# Final_Driver_Concept.net
KiCad netlist of a schematic drawn in EAGLE
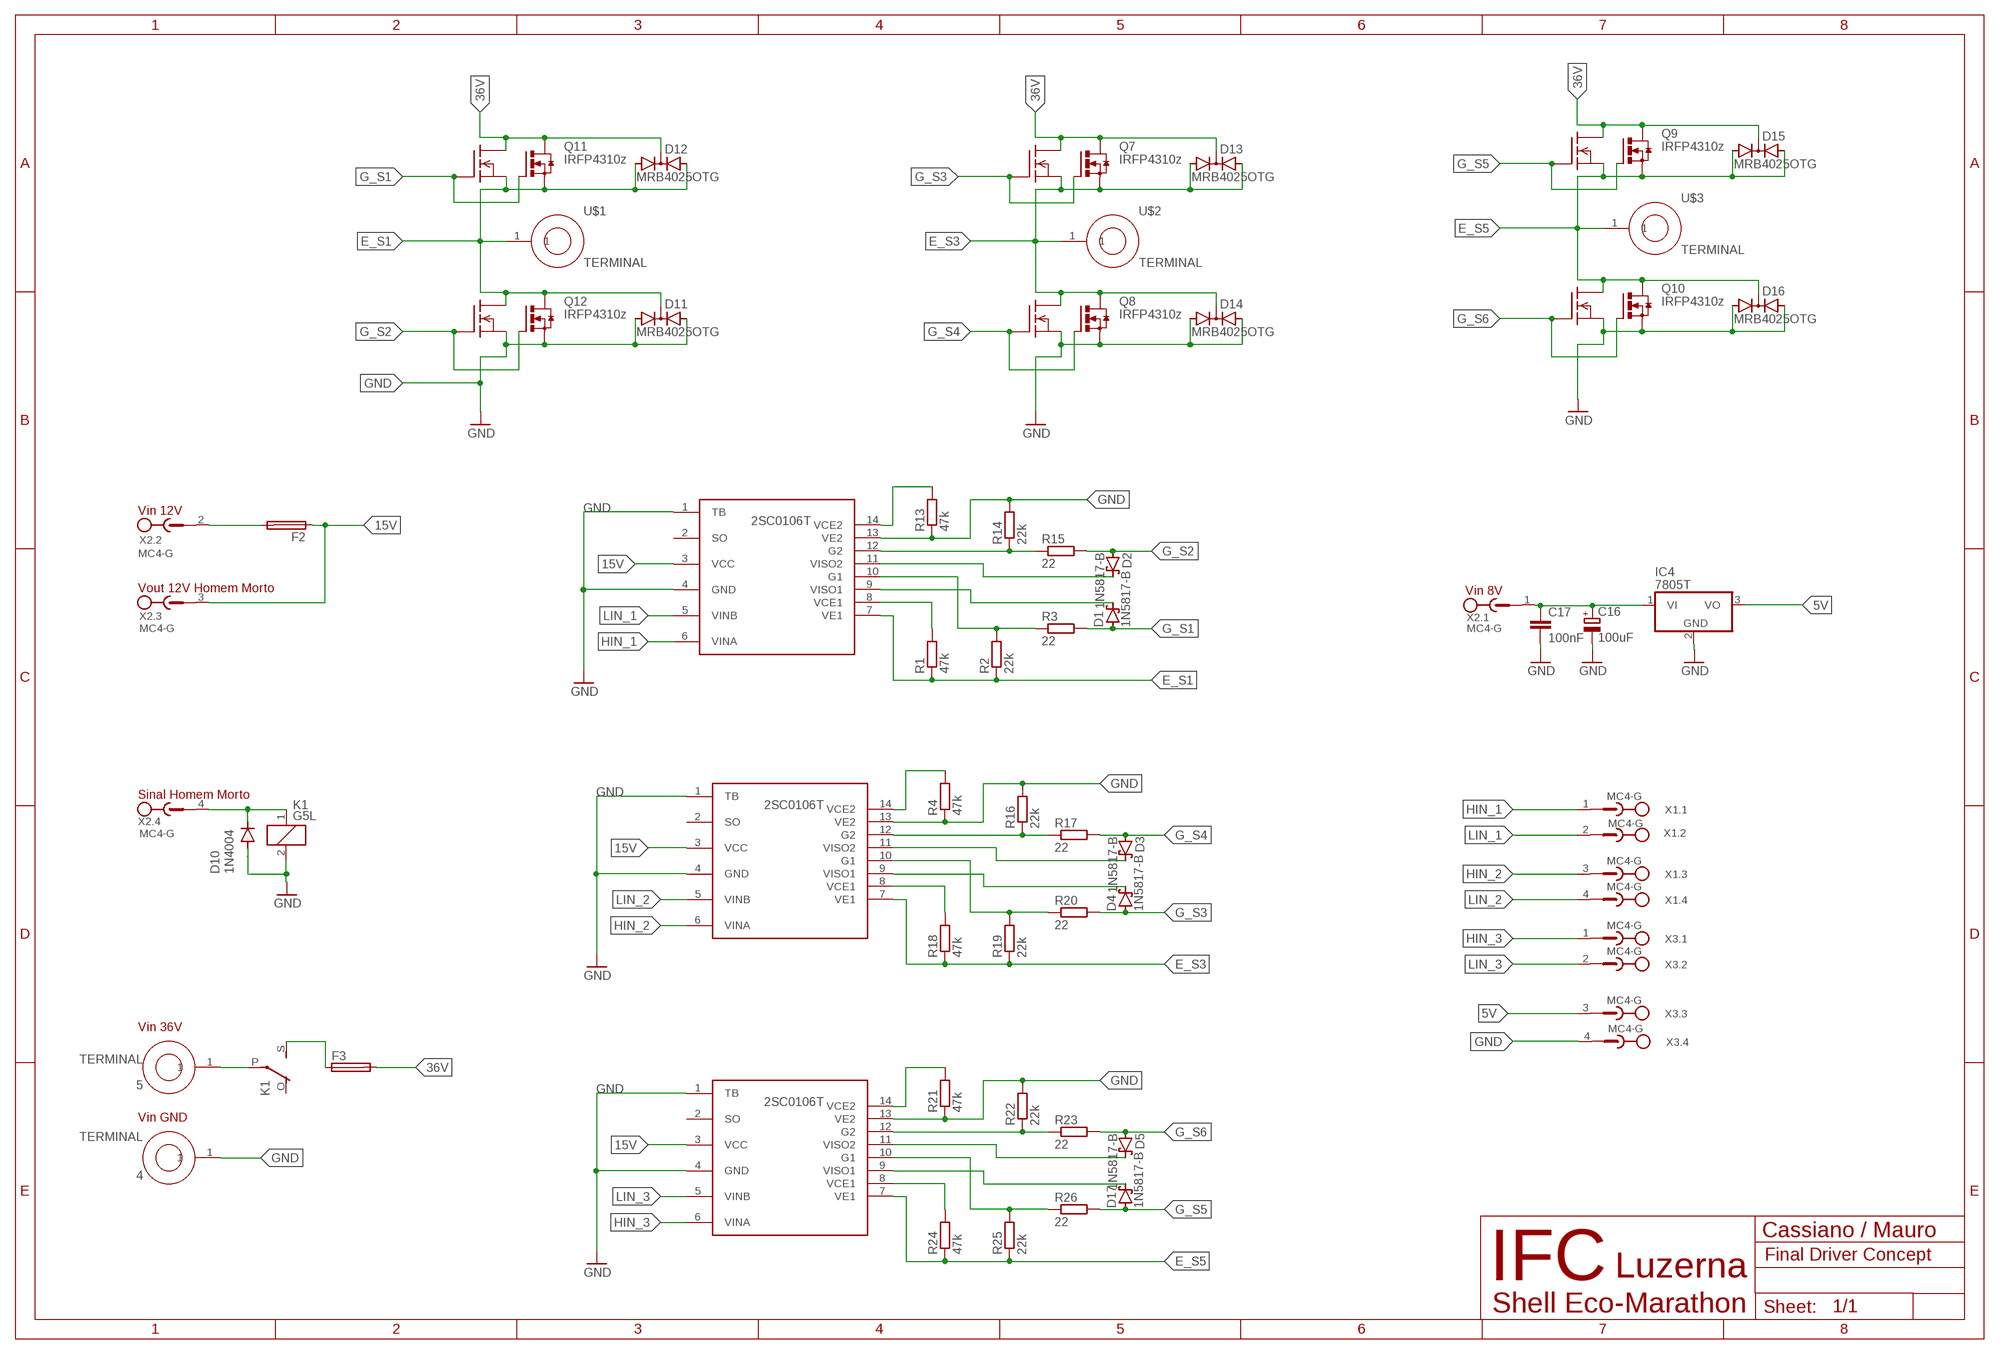
[diagram p0: schematic, sheet 1]

(export (version "E")
  (design (tool "Eeschema 10.0.6"))
  (components
    (comp (ref "4")
      (value "TERMINAL")
      (footprint "eagle-import:TERMINAL")
      (libsource (lib "eagle-import") (part "TERMINAL"))
    )
    (comp (ref "5")
      (value "TERMINAL")
      (footprint "eagle-import:TERMINAL")
      (libsource (lib "eagle-import") (part "TERMINAL"))
    )
    (comp (ref "C16")
      (value "100uF")
      (footprint "eagle-import:E2,5-7")
      (libsource (lib "eagle-import") (part "CPOL-EUE2.5-7"))
    )
    (comp (ref "C17")
      (value "100nF")
      (footprint "eagle-import:C050-045X075")
      (libsource (lib "eagle-import") (part "C-EU050-045X075"))
    )
    (comp (ref "D1")
      (value "1N5817-B")
      (footprint "eagle-import:DO41-7.6")
      (libsource (lib "eagle-import") (part "1N5817-B"))
    )
    (comp (ref "D2")
      (value "1N5817-B")
      (footprint "eagle-import:DO41-7.6")
      (libsource (lib "eagle-import") (part "1N5817-B"))
    )
    (comp (ref "D3")
      (value "1N5817-B")
      (footprint "eagle-import:DO41-7.6")
      (libsource (lib "eagle-import") (part "1N5817-B"))
    )
    (comp (ref "D4")
      (value "1N5817-B")
      (footprint "eagle-import:DO41-7.6")
      (libsource (lib "eagle-import") (part "1N5817-B"))
    )
    (comp (ref "D5")
      (value "1N5817-B")
      (footprint "eagle-import:DO41-7.6")
      (libsource (lib "eagle-import") (part "1N5817-B"))
    )
    (comp (ref "D10")
      (value "1N4004")
      (footprint "eagle-import:DO41-10")
      (libsource (lib "eagle-import") (part "1N4004"))
    )
    (comp (ref "D11")
      (value "MRB4025OTG")
      (footprint "eagle-import:TO220AB")
      (libsource (lib "eagle-import") (part "MUR620CT"))
    )
    (comp (ref "D12")
      (value "MRB4025OTG")
      (footprint "eagle-import:TO220AB")
      (libsource (lib "eagle-import") (part "MUR620CT"))
    )
    (comp (ref "D13")
      (value "MRB4025OTG")
      (footprint "eagle-import:TO220AB")
      (libsource (lib "eagle-import") (part "MUR620CT"))
    )
    (comp (ref "D14")
      (value "MRB4025OTG")
      (footprint "eagle-import:TO220AB")
      (libsource (lib "eagle-import") (part "MUR620CT"))
    )
    (comp (ref "D15")
      (value "MRB4025OTG")
      (footprint "eagle-import:TO220AB")
      (libsource (lib "eagle-import") (part "MUR620CT"))
    )
    (comp (ref "D16")
      (value "MRB4025OTG")
      (footprint "eagle-import:TO220AB")
      (libsource (lib "eagle-import") (part "MUR620CT"))
    )
    (comp (ref "D17")
      (value "1N5817-B")
      (footprint "eagle-import:DO41-7.6")
      (libsource (lib "eagle-import") (part "1N5817-B"))
    )
    (comp (ref "F2")
      (value "SH22,5A")
      (footprint "eagle-import:SH22,5A")
      (fields (field (name "MPN") "0031.7701.11"))
      (libsource (lib "eagle-import") (part "SH22,5A"))
    )
    (comp (ref "F3")
      (value "SH22,5A")
      (footprint "eagle-import:SH22,5A")
      (fields (field (name "MPN") "0031.7701.11"))
      (libsource (lib "eagle-import") (part "SH22,5A"))
    )
    (comp (ref "GATEDRIVER1")
      (value "2SC0106T1")
      (footprint "eagle-import:2SC0106T")
      (libsource (lib "eagle-import") (part "2SC0106T1"))
    )
    (comp (ref "GATEDRIVER2")
      (value "2SC0106T1")
      (footprint "eagle-import:2SC0106T")
      (libsource (lib "eagle-import") (part "2SC0106T1"))
    )
    (comp (ref "GATEDRIVER3")
      (value "2SC0106T1")
      (footprint "eagle-import:2SC0106T")
      (libsource (lib "eagle-import") (part "2SC0106T1"))
    )
    (comp (ref "IC4")
      (value "7805T")
      (footprint "eagle-import:TO220H")
      (libsource (lib "eagle-import") (part "78T05"))
    )
    (comp (ref "K1")
      (value "G5L")
      (footprint "eagle-import:G5LE")
      (libsource (lib "eagle-import") (part "G5L"))
    )
    (comp (ref "Q1")
      (value "IRF540")
      (footprint "eagle-import:TO220")
      (libsource (lib "eagle-import") (part "IRF540"))
    )
    (comp (ref "Q2")
      (value "IRF540")
      (footprint "eagle-import:TO220")
      (libsource (lib "eagle-import") (part "IRF540"))
    )
    (comp (ref "Q3")
      (value "IRF540")
      (footprint "eagle-import:TO220")
      (libsource (lib "eagle-import") (part "IRF540"))
    )
    (comp (ref "Q4")
      (value "IRF540")
      (footprint "eagle-import:TO220")
      (libsource (lib "eagle-import") (part "IRF540"))
    )
    (comp (ref "Q5")
      (value "IRF540")
      (footprint "eagle-import:TO220")
      (libsource (lib "eagle-import") (part "IRF540"))
    )
    (comp (ref "Q6")
      (value "IRF540")
      (footprint "eagle-import:TO220")
      (libsource (lib "eagle-import") (part "IRF540"))
    )
    (comp (ref "Q7")
      (value "IRFP4310z")
      (footprint "eagle-import:TO247BH")
      (libsource (lib "eagle-import") (part "IRFP240-H"))
    )
    (comp (ref "Q8")
      (value "IRFP4310z")
      (footprint "eagle-import:TO247BH")
      (libsource (lib "eagle-import") (part "IRFP240-H"))
    )
    (comp (ref "Q9")
      (value "IRFP4310z")
      (footprint "eagle-import:TO247BH")
      (libsource (lib "eagle-import") (part "IRFP240-H"))
    )
    (comp (ref "Q10")
      (value "IRFP4310z")
      (footprint "eagle-import:TO247BH")
      (libsource (lib "eagle-import") (part "IRFP240-H"))
    )
    (comp (ref "Q11")
      (value "IRFP4310z")
      (footprint "eagle-import:TO247BH")
      (libsource (lib "eagle-import") (part "IRFP240-H"))
    )
    (comp (ref "Q12")
      (value "IRFP4310z")
      (footprint "eagle-import:TO247BH")
      (libsource (lib "eagle-import") (part "IRFP240-H"))
    )
    (comp (ref "R1")
      (value "47k")
      (footprint "eagle-import:0204_7")
      (libsource (lib "eagle-import") (part "R-EU_0204/7"))
    )
    (comp (ref "R2")
      (value "22k")
      (footprint "eagle-import:0204_7")
      (libsource (lib "eagle-import") (part "R-EU_0204/7"))
    )
    (comp (ref "R3")
      (value "22")
      (footprint "eagle-import:0204_7")
      (libsource (lib "eagle-import") (part "R-EU_0204/7"))
    )
    (comp (ref "R4")
      (value "47k")
      (footprint "eagle-import:0204_7")
      (libsource (lib "eagle-import") (part "R-EU_0204/7"))
    )
    (comp (ref "R13")
      (value "47k")
      (footprint "eagle-import:0204_7")
      (libsource (lib "eagle-import") (part "R-EU_0204/7"))
    )
    (comp (ref "R14")
      (value "22k")
      (footprint "eagle-import:0204_7")
      (libsource (lib "eagle-import") (part "R-EU_0204/7"))
    )
    (comp (ref "R15")
      (value "22")
      (footprint "eagle-import:0204_7")
      (libsource (lib "eagle-import") (part "R-EU_0204/7"))
    )
    (comp (ref "R16")
      (value "22k")
      (footprint "eagle-import:0204_7")
      (libsource (lib "eagle-import") (part "R-EU_0204/7"))
    )
    (comp (ref "R17")
      (value "22")
      (footprint "eagle-import:0204_7")
      (libsource (lib "eagle-import") (part "R-EU_0204/7"))
    )
    (comp (ref "R18")
      (value "47k")
      (footprint "eagle-import:0204_7")
      (libsource (lib "eagle-import") (part "R-EU_0204/7"))
    )
    (comp (ref "R19")
      (value "22k")
      (footprint "eagle-import:0204_7")
      (libsource (lib "eagle-import") (part "R-EU_0204/7"))
    )
    (comp (ref "R20")
      (value "22")
      (footprint "eagle-import:0204_7")
      (libsource (lib "eagle-import") (part "R-EU_0204/7"))
    )
    (comp (ref "R21")
      (value "47k")
      (footprint "eagle-import:0204_7")
      (libsource (lib "eagle-import") (part "R-EU_0204/7"))
    )
    (comp (ref "R22")
      (value "22k")
      (footprint "eagle-import:0204_7")
      (libsource (lib "eagle-import") (part "R-EU_0204/7"))
    )
    (comp (ref "R23")
      (value "22")
      (footprint "eagle-import:0204_7")
      (libsource (lib "eagle-import") (part "R-EU_0204/7"))
    )
    (comp (ref "R24")
      (value "47k")
      (footprint "eagle-import:0204_7")
      (libsource (lib "eagle-import") (part "R-EU_0204/7"))
    )
    (comp (ref "R25")
      (value "22k")
      (footprint "eagle-import:0204_7")
      (libsource (lib "eagle-import") (part "R-EU_0204/7"))
    )
    (comp (ref "R26")
      (value "22")
      (footprint "eagle-import:0204_7")
      (libsource (lib "eagle-import") (part "R-EU_0204/7"))
    )
    (comp (ref "U$1")
      (value "TERMINAL")
      (footprint "eagle-import:TERMINAL")
      (libsource (lib "eagle-import") (part "TERMINAL"))
    )
    (comp (ref "U$2")
      (value "TERMINAL")
      (footprint "eagle-import:TERMINAL")
      (libsource (lib "eagle-import") (part "TERMINAL"))
    )
    (comp (ref "U$3")
      (value "TERMINAL")
      (footprint "eagle-import:TERMINAL")
      (libsource (lib "eagle-import") (part "TERMINAL"))
    )
    (comp (ref "X1")
      (value "MC4-G")
      (footprint "eagle-import:MC4-G")
      (libsource (lib "eagle-import") (part "MC4-G"))
    )
    (comp (ref "X2")
      (value "MC4-G")
      (footprint "eagle-import:MC4-G")
      (libsource (lib "eagle-import") (part "MC4-G"))
    )
    (comp (ref "X3")
      (value "MC4-G")
      (footprint "eagle-import:MC4-G")
      (libsource (lib "eagle-import") (part "MC4-G"))
    )
  )
  (nets
    (net (code "1") (name "5V") (class "Default")
      (node (ref "IC4") (pin "3") (pinfunction "VO_3") (pintype "passive"))
      (node (ref "X3") (pin "3") (pinfunction "SK_3") (pintype "passive"))
    )
    (net (code "2") (name "15V") (class "Default")
      (node (ref "F2") (pin "1") (pinfunction "1_1") (pintype "passive"))
      (node (ref "GATEDRIVER1") (pin "3") (pinfunction "VCC_3") (pintype "power_in"))
      (node (ref "GATEDRIVER2") (pin "3") (pinfunction "VCC_3") (pintype "power_in"))
      (node (ref "GATEDRIVER3") (pin "3") (pinfunction "VCC_3") (pintype "power_in"))
      (node (ref "X2") (pin "3") (pinfunction "SK_3") (pintype "passive"))
    )
    (net (code "3") (name "36V") (class "Default")
      (node (ref "D12") (pin "C") (pinfunction "C_C") (pintype "passive"))
      (node (ref "D13") (pin "C") (pinfunction "C_C") (pintype "passive"))
      (node (ref "D15") (pin "C") (pinfunction "C_C") (pintype "passive"))
      (node (ref "F3") (pin "2") (pinfunction "2_2") (pintype "passive"))
      (node (ref "Q1") (pin "2") (pinfunction "D_2") (pintype "passive"))
      (node (ref "Q11") (pin "D") (pinfunction "D_D") (pintype "passive"))
      (node (ref "Q3") (pin "2") (pinfunction "D_2") (pintype "passive"))
      (node (ref "Q5") (pin "2") (pinfunction "D_2") (pintype "passive"))
      (node (ref "Q7") (pin "D") (pinfunction "D_D") (pintype "passive"))
      (node (ref "Q9") (pin "D") (pinfunction "D_D") (pintype "passive"))
    )
    (net (code "4") (name "E_S1") (class "Default")
      (node (ref "D11") (pin "C") (pinfunction "C_C") (pintype "passive"))
      (node (ref "D12") (pin "A1") (pinfunction "A1_A1") (pintype "passive"))
      (node (ref "D12") (pin "A2") (pinfunction "A2_A2") (pintype "passive"))
      (node (ref "GATEDRIVER1") (pin "7") (pinfunction "VE1_7") (pintype "bidirectional"))
      (node (ref "Q1") (pin "3") (pinfunction "S_3") (pintype "passive"))
      (node (ref "Q11") (pin "S") (pinfunction "S_S") (pintype "passive"))
      (node (ref "Q12") (pin "D") (pinfunction "D_D") (pintype "passive"))
      (node (ref "Q2") (pin "2") (pinfunction "D_2") (pintype "passive"))
      (node (ref "R1") (pin "1") (pinfunction "1_1") (pintype "passive"))
      (node (ref "R2") (pin "1") (pinfunction "1_1") (pintype "passive"))
      (node (ref "U$1") (pin "1") (pinfunction "1_1") (pintype "bidirectional"))
    )
    (net (code "5") (name "E_S3") (class "Default")
      (node (ref "D13") (pin "A1") (pinfunction "A1_A1") (pintype "passive"))
      (node (ref "D13") (pin "A2") (pinfunction "A2_A2") (pintype "passive"))
      (node (ref "D14") (pin "C") (pinfunction "C_C") (pintype "passive"))
      (node (ref "GATEDRIVER2") (pin "7") (pinfunction "VE1_7") (pintype "bidirectional"))
      (node (ref "Q3") (pin "3") (pinfunction "S_3") (pintype "passive"))
      (node (ref "Q4") (pin "2") (pinfunction "D_2") (pintype "passive"))
      (node (ref "Q7") (pin "S") (pinfunction "S_S") (pintype "passive"))
      (node (ref "Q8") (pin "D") (pinfunction "D_D") (pintype "passive"))
      (node (ref "R18") (pin "1") (pinfunction "1_1") (pintype "passive"))
      (node (ref "R19") (pin "1") (pinfunction "1_1") (pintype "passive"))
      (node (ref "U$2") (pin "1") (pinfunction "1_1") (pintype "bidirectional"))
    )
    (net (code "6") (name "E_S5") (class "Default")
      (node (ref "D15") (pin "A1") (pinfunction "A1_A1") (pintype "passive"))
      (node (ref "D15") (pin "A2") (pinfunction "A2_A2") (pintype "passive"))
      (node (ref "D16") (pin "C") (pinfunction "C_C") (pintype "passive"))
      (node (ref "GATEDRIVER3") (pin "7") (pinfunction "VE1_7") (pintype "bidirectional"))
      (node (ref "Q10") (pin "D") (pinfunction "D_D") (pintype "passive"))
      (node (ref "Q5") (pin "3") (pinfunction "S_3") (pintype "passive"))
      (node (ref "Q6") (pin "2") (pinfunction "D_2") (pintype "passive"))
      (node (ref "Q9") (pin "S") (pinfunction "S_S") (pintype "passive"))
      (node (ref "R24") (pin "1") (pinfunction "1_1") (pintype "passive"))
      (node (ref "R25") (pin "1") (pinfunction "1_1") (pintype "passive"))
      (node (ref "U$3") (pin "1") (pinfunction "1_1") (pintype "bidirectional"))
    )
    (net (code "7") (name "GND") (class "Default")
      (node (ref "4") (pin "1") (pinfunction "1_1") (pintype "bidirectional"))
      (node (ref "C16") (pin "-") (pinfunction "-_-") (pintype "passive"))
      (node (ref "C17") (pin "2") (pinfunction "2_2") (pintype "passive"))
      (node (ref "D10") (pin "A") (pinfunction "A_A") (pintype "passive"))
      (node (ref "D11") (pin "A1") (pinfunction "A1_A1") (pintype "passive"))
      (node (ref "D11") (pin "A2") (pinfunction "A2_A2") (pintype "passive"))
      (node (ref "D14") (pin "A1") (pinfunction "A1_A1") (pintype "passive"))
      (node (ref "D14") (pin "A2") (pinfunction "A2_A2") (pintype "passive"))
      (node (ref "D16") (pin "A1") (pinfunction "A1_A1") (pintype "passive"))
      (node (ref "D16") (pin "A2") (pinfunction "A2_A2") (pintype "passive"))
      (node (ref "GATEDRIVER1") (pin "1") (pinfunction "TB_1") (pintype "bidirectional"))
      (node (ref "GATEDRIVER1") (pin "13") (pinfunction "VE2_13") (pintype "output"))
      (node (ref "GATEDRIVER1") (pin "4") (pinfunction "GND_4") (pintype "power_in"))
      (node (ref "GATEDRIVER2") (pin "1") (pinfunction "TB_1") (pintype "bidirectional"))
      (node (ref "GATEDRIVER2") (pin "13") (pinfunction "VE2_13") (pintype "output"))
      (node (ref "GATEDRIVER2") (pin "4") (pinfunction "GND_4") (pintype "power_in"))
      (node (ref "GATEDRIVER3") (pin "1") (pinfunction "TB_1") (pintype "bidirectional"))
      (node (ref "GATEDRIVER3") (pin "13") (pinfunction "VE2_13") (pintype "output"))
      (node (ref "GATEDRIVER3") (pin "4") (pinfunction "GND_4") (pintype "power_in"))
      (node (ref "IC4") (pin "2") (pinfunction "GND_2") (pintype "passive"))
      (node (ref "K1") (pin "2") (pinfunction "2_2") (pintype "passive"))
      (node (ref "Q10") (pin "S") (pinfunction "S_S") (pintype "passive"))
      (node (ref "Q12") (pin "S") (pinfunction "S_S") (pintype "passive"))
      (node (ref "Q2") (pin "3") (pinfunction "S_3") (pintype "passive"))
      (node (ref "Q4") (pin "3") (pinfunction "S_3") (pintype "passive"))
      (node (ref "Q6") (pin "3") (pinfunction "S_3") (pintype "passive"))
      (node (ref "Q8") (pin "S") (pinfunction "S_S") (pintype "passive"))
      (node (ref "R13") (pin "1") (pinfunction "1_1") (pintype "passive"))
      (node (ref "R14") (pin "2") (pinfunction "2_2") (pintype "passive"))
      (node (ref "R16") (pin "2") (pinfunction "2_2") (pintype "passive"))
      (node (ref "R21") (pin "1") (pinfunction "1_1") (pintype "passive"))
      (node (ref "R22") (pin "2") (pinfunction "2_2") (pintype "passive"))
      (node (ref "R4") (pin "1") (pinfunction "1_1") (pintype "passive"))
      (node (ref "X3") (pin "4") (pinfunction "SK_4") (pintype "passive"))
    )
    (net (code "8") (name "G_S1") (class "Default")
      (node (ref "D1") (pin "A") (pinfunction "A_A") (pintype "passive"))
      (node (ref "Q1") (pin "1") (pinfunction "G_1") (pintype "passive"))
      (node (ref "Q11") (pin "G") (pinfunction "G_G") (pintype "passive"))
      (node (ref "R3") (pin "2") (pinfunction "2_2") (pintype "passive"))
    )
    (net (code "9") (name "G_S2") (class "Default")
      (node (ref "D2") (pin "A") (pinfunction "A_A") (pintype "passive"))
      (node (ref "Q12") (pin "G") (pinfunction "G_G") (pintype "passive"))
      (node (ref "Q2") (pin "1") (pinfunction "G_1") (pintype "passive"))
      (node (ref "R15") (pin "2") (pinfunction "2_2") (pintype "passive"))
    )
    (net (code "10") (name "G_S3") (class "Default")
      (node (ref "D4") (pin "A") (pinfunction "A_A") (pintype "passive"))
      (node (ref "Q3") (pin "1") (pinfunction "G_1") (pintype "passive"))
      (node (ref "Q7") (pin "G") (pinfunction "G_G") (pintype "passive"))
      (node (ref "R20") (pin "2") (pinfunction "2_2") (pintype "passive"))
    )
    (net (code "11") (name "G_S4") (class "Default")
      (node (ref "D3") (pin "A") (pinfunction "A_A") (pintype "passive"))
      (node (ref "Q4") (pin "1") (pinfunction "G_1") (pintype "passive"))
      (node (ref "Q8") (pin "G") (pinfunction "G_G") (pintype "passive"))
      (node (ref "R17") (pin "2") (pinfunction "2_2") (pintype "passive"))
    )
    (net (code "12") (name "G_S5") (class "Default")
      (node (ref "D17") (pin "A") (pinfunction "A_A") (pintype "passive"))
      (node (ref "Q5") (pin "1") (pinfunction "G_1") (pintype "passive"))
      (node (ref "Q9") (pin "G") (pinfunction "G_G") (pintype "passive"))
      (node (ref "R26") (pin "2") (pinfunction "2_2") (pintype "passive"))
    )
    (net (code "13") (name "G_S6") (class "Default")
      (node (ref "D5") (pin "A") (pinfunction "A_A") (pintype "passive"))
      (node (ref "Q10") (pin "G") (pinfunction "G_G") (pintype "passive"))
      (node (ref "Q6") (pin "1") (pinfunction "G_1") (pintype "passive"))
      (node (ref "R23") (pin "2") (pinfunction "2_2") (pintype "passive"))
    )
    (net (code "14") (name "HIN_1") (class "Default")
      (node (ref "GATEDRIVER1") (pin "6") (pinfunction "VINA_6") (pintype "input"))
      (node (ref "X1") (pin "1") (pinfunction "SK_1") (pintype "passive"))
    )
    (net (code "15") (name "HIN_2") (class "Default")
      (node (ref "GATEDRIVER2") (pin "6") (pinfunction "VINA_6") (pintype "input"))
      (node (ref "X1") (pin "3") (pinfunction "SK_3") (pintype "passive"))
    )
    (net (code "16") (name "HIN_3") (class "Default")
      (node (ref "GATEDRIVER3") (pin "6") (pinfunction "VINA_6") (pintype "input"))
      (node (ref "X3") (pin "1") (pinfunction "SK_1") (pintype "passive"))
    )
    (net (code "17") (name "LIN_1") (class "Default")
      (node (ref "GATEDRIVER1") (pin "5") (pinfunction "VINB_5") (pintype "input"))
      (node (ref "X1") (pin "2") (pinfunction "SK_2") (pintype "passive"))
    )
    (net (code "18") (name "LIN_2") (class "Default")
      (node (ref "GATEDRIVER2") (pin "5") (pinfunction "VINB_5") (pintype "input"))
      (node (ref "X1") (pin "4") (pinfunction "SK_4") (pintype "passive"))
    )
    (net (code "19") (name "LIN_3") (class "Default")
      (node (ref "GATEDRIVER3") (pin "5") (pinfunction "VINB_5") (pintype "input"))
      (node (ref "X3") (pin "2") (pinfunction "SK_2") (pintype "passive"))
    )
    (net (code "20") (name "Net-(5-Pad1)") (class "Default")
      (node (ref "5") (pin "1") (pinfunction "1_1") (pintype "bidirectional"))
      (node (ref "K1") (pin "P") (pinfunction "P_P") (pintype "passive"))
    )
    (net (code "21") (name "Net-(F3-Pad1)") (class "Default")
      (node (ref "F3") (pin "1") (pinfunction "1_1") (pintype "passive"))
      (node (ref "K1") (pin "S") (pinfunction "S_S") (pintype "passive"))
    )
    (net (code "22") (name "Net-(GATEDRIVER1-G1)") (class "Default")
      (node (ref "GATEDRIVER1") (pin "10") (pinfunction "G1_10") (pintype "output"))
      (node (ref "R2") (pin "2") (pinfunction "2_2") (pintype "passive"))
      (node (ref "R3") (pin "1") (pinfunction "1_1") (pintype "passive"))
    )
    (net (code "23") (name "Net-(GATEDRIVER1-G2)") (class "Default")
      (node (ref "GATEDRIVER1") (pin "12") (pinfunction "G2_12") (pintype "output"))
      (node (ref "R14") (pin "1") (pinfunction "1_1") (pintype "passive"))
      (node (ref "R15") (pin "1") (pinfunction "1_1") (pintype "passive"))
    )
    (net (code "24") (name "Net-(GATEDRIVER1-VCE1)") (class "Default")
      (node (ref "GATEDRIVER1") (pin "8") (pinfunction "VCE1_8") (pintype "bidirectional"))
      (node (ref "R1") (pin "2") (pinfunction "2_2") (pintype "passive"))
    )
    (net (code "25") (name "Net-(GATEDRIVER1-VCE2)") (class "Default")
      (node (ref "GATEDRIVER1") (pin "14") (pinfunction "VCE2_14") (pintype "output"))
      (node (ref "R13") (pin "2") (pinfunction "2_2") (pintype "passive"))
    )
    (net (code "26") (name "Net-(GATEDRIVER1-VISO1)") (class "Default")
      (node (ref "D1") (pin "C") (pinfunction "C_C") (pintype "passive"))
      (node (ref "GATEDRIVER1") (pin "9") (pinfunction "VISO1_9") (pintype "bidirectional"))
    )
    (net (code "27") (name "Net-(GATEDRIVER1-VISO2)") (class "Default")
      (node (ref "D2") (pin "C") (pinfunction "C_C") (pintype "passive"))
      (node (ref "GATEDRIVER1") (pin "11") (pinfunction "VISO2_11") (pintype "bidirectional"))
    )
    (net (code "28") (name "Net-(GATEDRIVER2-G1)") (class "Default")
      (node (ref "GATEDRIVER2") (pin "10") (pinfunction "G1_10") (pintype "output"))
      (node (ref "R19") (pin "2") (pinfunction "2_2") (pintype "passive"))
      (node (ref "R20") (pin "1") (pinfunction "1_1") (pintype "passive"))
    )
    (net (code "29") (name "Net-(GATEDRIVER2-G2)") (class "Default")
      (node (ref "GATEDRIVER2") (pin "12") (pinfunction "G2_12") (pintype "output"))
      (node (ref "R16") (pin "1") (pinfunction "1_1") (pintype "passive"))
      (node (ref "R17") (pin "1") (pinfunction "1_1") (pintype "passive"))
    )
    (net (code "30") (name "Net-(GATEDRIVER2-VCE1)") (class "Default")
      (node (ref "GATEDRIVER2") (pin "8") (pinfunction "VCE1_8") (pintype "bidirectional"))
      (node (ref "R18") (pin "2") (pinfunction "2_2") (pintype "passive"))
    )
    (net (code "31") (name "Net-(GATEDRIVER2-VCE2)") (class "Default")
      (node (ref "GATEDRIVER2") (pin "14") (pinfunction "VCE2_14") (pintype "output"))
      (node (ref "R4") (pin "2") (pinfunction "2_2") (pintype "passive"))
    )
    (net (code "32") (name "Net-(GATEDRIVER2-VISO1)") (class "Default")
      (node (ref "D4") (pin "C") (pinfunction "C_C") (pintype "passive"))
      (node (ref "GATEDRIVER2") (pin "9") (pinfunction "VISO1_9") (pintype "bidirectional"))
    )
    (net (code "33") (name "Net-(GATEDRIVER2-VISO2)") (class "Default")
      (node (ref "D3") (pin "C") (pinfunction "C_C") (pintype "passive"))
      (node (ref "GATEDRIVER2") (pin "11") (pinfunction "VISO2_11") (pintype "bidirectional"))
    )
    (net (code "34") (name "Net-(GATEDRIVER3-G1)") (class "Default")
      (node (ref "GATEDRIVER3") (pin "10") (pinfunction "G1_10") (pintype "output"))
      (node (ref "R25") (pin "2") (pinfunction "2_2") (pintype "passive"))
      (node (ref "R26") (pin "1") (pinfunction "1_1") (pintype "passive"))
    )
    (net (code "35") (name "Net-(GATEDRIVER3-G2)") (class "Default")
      (node (ref "GATEDRIVER3") (pin "12") (pinfunction "G2_12") (pintype "output"))
      (node (ref "R22") (pin "1") (pinfunction "1_1") (pintype "passive"))
      (node (ref "R23") (pin "1") (pinfunction "1_1") (pintype "passive"))
    )
    (net (code "36") (name "Net-(GATEDRIVER3-VCE1)") (class "Default")
      (node (ref "GATEDRIVER3") (pin "8") (pinfunction "VCE1_8") (pintype "bidirectional"))
      (node (ref "R24") (pin "2") (pinfunction "2_2") (pintype "passive"))
    )
    (net (code "37") (name "Net-(GATEDRIVER3-VCE2)") (class "Default")
      (node (ref "GATEDRIVER3") (pin "14") (pinfunction "VCE2_14") (pintype "output"))
      (node (ref "R21") (pin "2") (pinfunction "2_2") (pintype "passive"))
    )
    (net (code "38") (name "Net-(GATEDRIVER3-VISO1)") (class "Default")
      (node (ref "D17") (pin "C") (pinfunction "C_C") (pintype "passive"))
      (node (ref "GATEDRIVER3") (pin "9") (pinfunction "VISO1_9") (pintype "bidirectional"))
    )
    (net (code "39") (name "Net-(GATEDRIVER3-VISO2)") (class "Default")
      (node (ref "D5") (pin "C") (pinfunction "C_C") (pintype "passive"))
      (node (ref "GATEDRIVER3") (pin "11") (pinfunction "VISO2_11") (pintype "bidirectional"))
    )
    (net (code "40") (name "Net-(IC4-VI)") (class "Default")
      (node (ref "C16") (pin "+") (pinfunction "+_+") (pintype "passive"))
      (node (ref "C17") (pin "1") (pinfunction "1_1") (pintype "passive"))
      (node (ref "IC4") (pin "1") (pinfunction "VI_1") (pintype "input"))
      (node (ref "X2") (pin "1") (pinfunction "SK_1") (pintype "passive"))
    )
    (net (code "41") (name "Net-(X2B-SK)") (class "Default")
      (node (ref "F2") (pin "2") (pinfunction "2_2") (pintype "passive"))
      (node (ref "X2") (pin "2") (pinfunction "SK_2") (pintype "passive"))
    )
    (net (code "42") (name "Net-(X2D-SK)") (class "Default")
      (node (ref "D10") (pin "C") (pinfunction "C_C") (pintype "passive"))
      (node (ref "K1") (pin "1") (pinfunction "1_1") (pintype "passive"))
      (node (ref "X2") (pin "4") (pinfunction "SK_4") (pintype "passive"))
    )
    (net (code "43") (name "unconnected-(GATEDRIVER1-SO-Pad2)") (class "Default")
      (node (ref "GATEDRIVER1") (pin "2") (pinfunction "SO_2") (pintype "bidirectional"))
    )
    (net (code "44") (name "unconnected-(GATEDRIVER2-SO-Pad2)") (class "Default")
      (node (ref "GATEDRIVER2") (pin "2") (pinfunction "SO_2") (pintype "bidirectional"))
    )
    (net (code "45") (name "unconnected-(GATEDRIVER3-SO-Pad2)") (class "Default")
      (node (ref "GATEDRIVER3") (pin "2") (pinfunction "SO_2") (pintype "bidirectional"))
    )
    (net (code "46") (name "unconnected-(K1-PadO)") (class "Default")
      (node (ref "K1") (pin "O") (pinfunction "O_O") (pintype "passive"))
    )
  )
)
